# arduino-lockitron-nfc.net
KiCad netlist of a schematic drawn in EAGLE
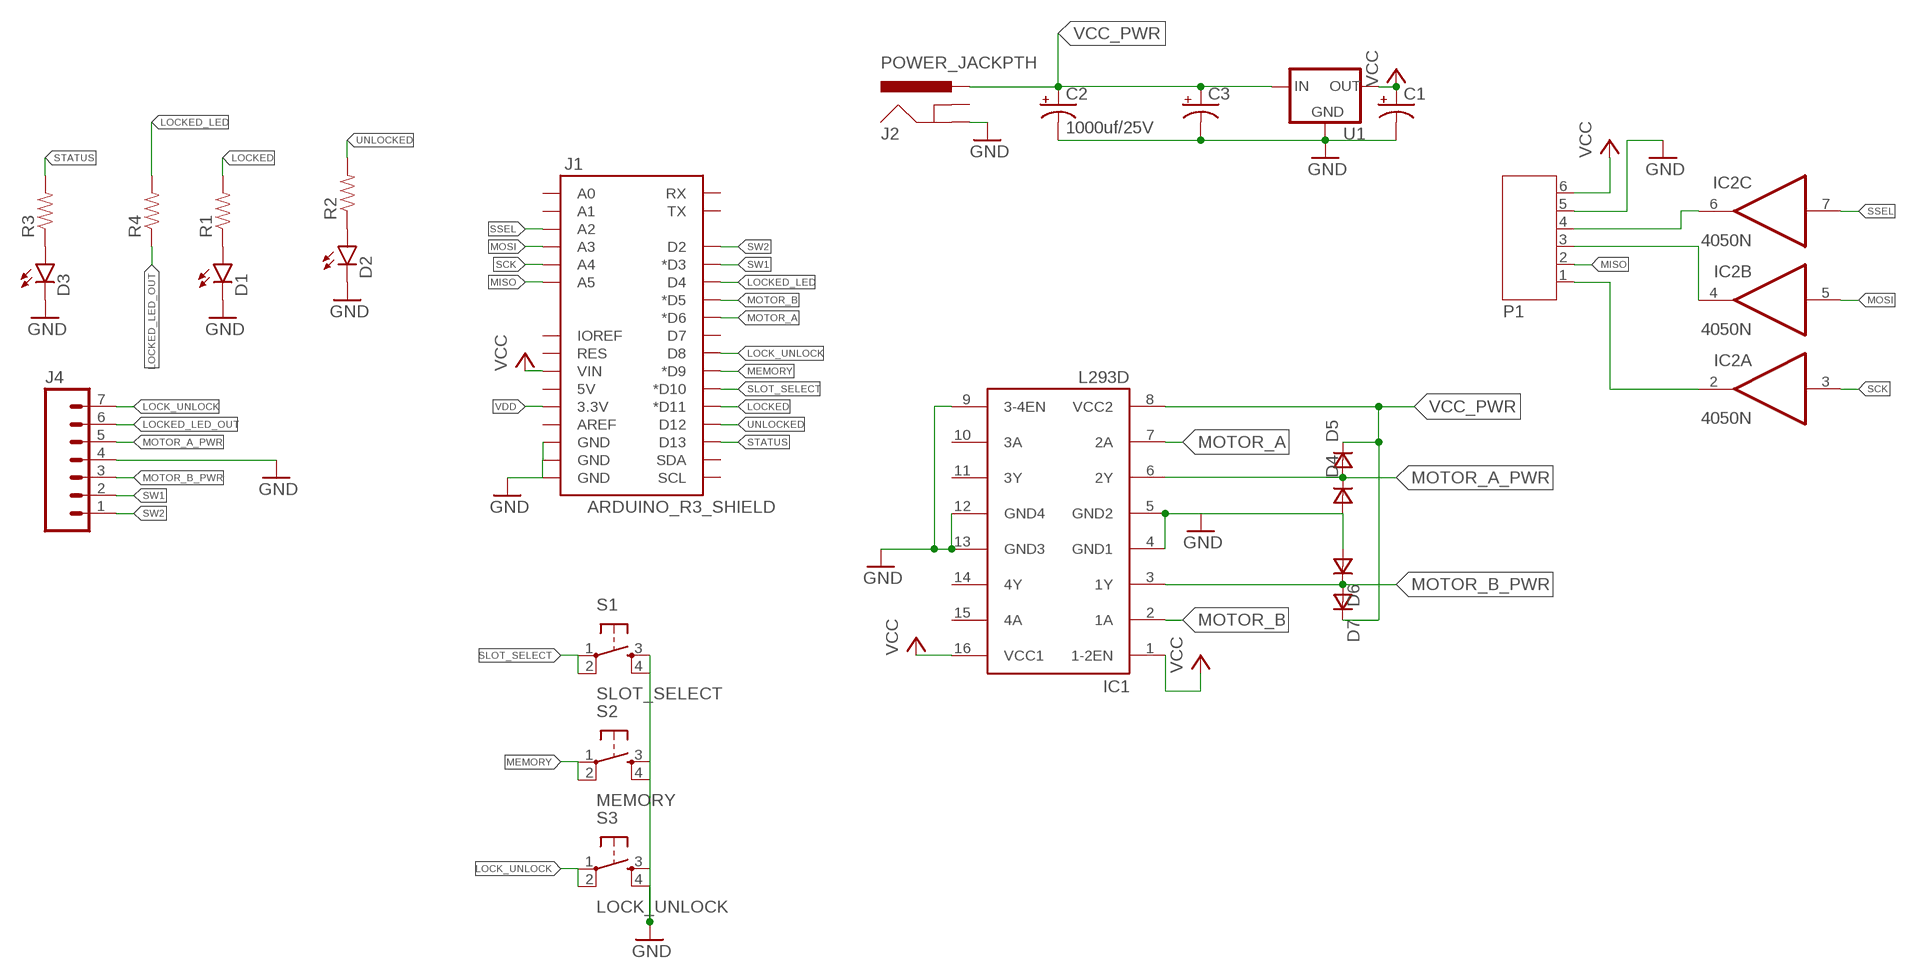
[diagram p0: schematic, sheet 1]

(export (version "E")
  (design (tool "Eeschema 10.0.6"))
  (components
    (comp (ref "C1")
      (value "47UF-50V-20%(ELECT)")
      (footprint "eagle-import:PANASONIC_D")
      (libsource (lib "eagle-import") (part "47UF-50V-20%(ELECT)"))
    )
    (comp (ref "C2")
      (value "1000uf/25V")
      (footprint "eagle-import:CPOL-RADIAL-1000UF-25V-KIT")
      (libsource (lib "eagle-import") (part "1000UF-25V(PTH)KIT"))
    )
    (comp (ref "C3")
      (value "47UF-50V-20%(ELECT)")
      (footprint "eagle-import:PANASONIC_D")
      (libsource (lib "eagle-import") (part "47UF-50V-20%(ELECT)"))
    )
    (comp (ref "D1")
      (value "LED0603")
      (footprint "eagle-import:LED-0603")
      (libsource (lib "eagle-import") (part "LED0603"))
    )
    (comp (ref "D2")
      (value "LED0603")
      (footprint "eagle-import:LED-0603")
      (libsource (lib "eagle-import") (part "LED0603"))
    )
    (comp (ref "D3")
      (value "LED0603")
      (footprint "eagle-import:LED-0603")
      (libsource (lib "eagle-import") (part "LED0603"))
    )
    (comp (ref "D4")
      (value "DSOD323")
      (footprint "eagle-import:SOD323")
      (fields (field (name "MPN") "CDSOD323-T05C"))
      (libsource (lib "eagle-import") (part "DSOD323"))
    )
    (comp (ref "D5")
      (value "DSOD323")
      (footprint "eagle-import:SOD323")
      (fields (field (name "MPN") "CDSOD323-T05C"))
      (libsource (lib "eagle-import") (part "DSOD323"))
    )
    (comp (ref "D6")
      (value "DSOD323")
      (footprint "eagle-import:SOD323")
      (fields (field (name "MPN") "CDSOD323-T05C"))
      (libsource (lib "eagle-import") (part "DSOD323"))
    )
    (comp (ref "D7")
      (value "DSOD323")
      (footprint "eagle-import:SOD323")
      (fields (field (name "MPN") "CDSOD323-T05C"))
      (libsource (lib "eagle-import") (part "DSOD323"))
    )
    (comp (ref "IC1")
      (value "L293D")
      (footprint "eagle-import:DIL16")
      (libsource (lib "eagle-import") (part "L293D"))
    )
    (comp (ref "IC2")
      (value "4050N")
      (footprint "eagle-import:DIL16")
      (libsource (lib "eagle-import") (part "4050N"))
    )
    (comp (ref "J1")
      (value "ARDUINO_R3_SHIELD")
      (footprint "eagle-import:UNO_R3_SHIELD")
      (libsource (lib "eagle-import") (part "ARDUINO_R3_SHIELD"))
    )
    (comp (ref "J2")
      (value "POWER_JACKPTH")
      (footprint "eagle-import:POWER_JACK_PTH")
      (libsource (lib "eagle-import") (part "POWER_JACKPTH"))
    )
    (comp (ref "J4")
      (value "M07LONGPADS")
      (footprint "eagle-import:1X07_LONGPADS")
      (libsource (lib "eagle-import") (part "M07LONGPADS"))
    )
    (comp (ref "P1")
      (value "JST-PH6")
      (footprint "eagle-import:JST-PH6")
      (libsource (lib "eagle-import") (part "JST-PH6"))
    )
    (comp (ref "R1")
      (value "RESISTOR0603")
      (footprint "eagle-import:0603-RES")
      (libsource (lib "eagle-import") (part "RESISTOR0603"))
    )
    (comp (ref "R2")
      (value "RESISTOR0603")
      (footprint "eagle-import:0603-RES")
      (libsource (lib "eagle-import") (part "RESISTOR0603"))
    )
    (comp (ref "R3")
      (value "RESISTOR0603")
      (footprint "eagle-import:0603-RES")
      (libsource (lib "eagle-import") (part "RESISTOR0603"))
    )
    (comp (ref "R4")
      (value "RESISTOR0603")
      (footprint "eagle-import:0603-RES")
      (libsource (lib "eagle-import") (part "RESISTOR0603"))
    )
    (comp (ref "S1")
      (value "SLOT_SELECT")
      (footprint "eagle-import:TACTILE-SWITCH-SMD")
      (libsource (lib "eagle-import") (part "TAC_SWITCHSMD"))
    )
    (comp (ref "S2")
      (value "MEMORY")
      (footprint "eagle-import:TACTILE-SWITCH-SMD")
      (libsource (lib "eagle-import") (part "TAC_SWITCHSMD"))
    )
    (comp (ref "S3")
      (value "LOCK_UNLOCK")
      (footprint "eagle-import:TACTILE-SWITCH-SMD")
      (libsource (lib "eagle-import") (part "TAC_SWITCHSMD"))
    )
    (comp (ref "U1")
      (value "V_REG_78XXSIDE")
      (footprint "eagle-import:78XXL")
      (libsource (lib "eagle-import") (part "V_REG_78XXSIDE"))
    )
  )
  (nets
    (net (code "1") (name "GND") (class "Default")
      (node (ref "C1") (pin "-") (pinfunction "-_-") (pintype "passive"))
      (node (ref "C2") (pin "-") (pinfunction "-_-") (pintype "passive"))
      (node (ref "C3") (pin "-") (pinfunction "-_-") (pintype "passive"))
      (node (ref "D1") (pin "C") (pinfunction "C_C") (pintype "passive"))
      (node (ref "D2") (pin "C") (pinfunction "C_C") (pintype "passive"))
      (node (ref "D3") (pin "C") (pinfunction "C_C") (pintype "passive"))
      (node (ref "D4") (pin "2") (pinfunction "A_2") (pintype "passive"))
      (node (ref "D6") (pin "2") (pinfunction "A_2") (pintype "passive"))
      (node (ref "IC1") (pin "12") (pinfunction "GND4_12") (pintype "power_in"))
      (node (ref "IC1") (pin "13") (pinfunction "GND3_13") (pintype "power_in"))
      (node (ref "IC1") (pin "4") (pinfunction "GND1_4") (pintype "power_in"))
      (node (ref "IC1") (pin "5") (pinfunction "GND2_5") (pintype "power_in"))
      (node (ref "IC1") (pin "9") (pinfunction "3-4EN_9") (pintype "input"))
      (node (ref "J1") (pin "GND@0") (pinfunction "GND_GND@0") (pintype "bidirectional"))
      (node (ref "J1") (pin "GND@1") (pinfunction "GND_GND@1") (pintype "bidirectional"))
      (node (ref "J1") (pin "GND@2") (pinfunction "GND_GND@2") (pintype "bidirectional"))
      (node (ref "J2") (pin "GND") (pinfunction "GND_GND") (pintype "bidirectional"))
      (node (ref "J4") (pin "4") (pinfunction "4_4") (pintype "passive"))
      (node (ref "P1") (pin "5") (pinfunction "5_5") (pintype "passive"))
      (node (ref "S1") (pin "3") (pinfunction "3_3") (pintype "passive"))
      (node (ref "S1") (pin "4") (pinfunction "4_4") (pintype "passive"))
      (node (ref "S2") (pin "3") (pinfunction "3_3") (pintype "passive"))
      (node (ref "S2") (pin "4") (pinfunction "4_4") (pintype "passive"))
      (node (ref "S3") (pin "3") (pinfunction "3_3") (pintype "passive"))
      (node (ref "S3") (pin "4") (pinfunction "4_4") (pintype "passive"))
      (node (ref "U1") (pin "GND") (pinfunction "GND_GND") (pintype "input"))
    )
    (net (code "2") (name "LOCKED") (class "Default")
      (node (ref "J1") (pin "D11") (pinfunction "*D11_D11") (pintype "bidirectional"))
      (node (ref "R1") (pin "2") (pinfunction "2_2") (pintype "passive"))
    )
    (net (code "3") (name "LOCKED_LED") (class "Default")
      (node (ref "J1") (pin "D4") (pinfunction "D4_D4") (pintype "bidirectional"))
      (node (ref "R4") (pin "2") (pinfunction "2_2") (pintype "passive"))
    )
    (net (code "4") (name "LOCKED_LED_OUT") (class "Default")
      (node (ref "J4") (pin "6") (pinfunction "6_6") (pintype "passive"))
      (node (ref "R4") (pin "1") (pinfunction "1_1") (pintype "passive"))
    )
    (net (code "5") (name "LOCK_UNLOCK") (class "Default")
      (node (ref "J1") (pin "D8") (pinfunction "D8_D8") (pintype "bidirectional"))
      (node (ref "J4") (pin "7") (pinfunction "7_7") (pintype "passive"))
      (node (ref "S3") (pin "1") (pinfunction "1_1") (pintype "passive"))
      (node (ref "S3") (pin "2") (pinfunction "2_2") (pintype "passive"))
    )
    (net (code "6") (name "MEMORY") (class "Default")
      (node (ref "J1") (pin "D9") (pinfunction "*D9_D9") (pintype "bidirectional"))
      (node (ref "S2") (pin "1") (pinfunction "1_1") (pintype "passive"))
      (node (ref "S2") (pin "2") (pinfunction "2_2") (pintype "passive"))
    )
    (net (code "7") (name "MISO") (class "Default")
      (node (ref "J1") (pin "A5") (pinfunction "A5_A5") (pintype "bidirectional"))
      (node (ref "P1") (pin "2") (pinfunction "2_2") (pintype "passive"))
    )
    (net (code "8") (name "MOSI") (class "Default")
      (node (ref "IC2") (pin "5") (pinfunction "I_5") (pintype "input"))
      (node (ref "J1") (pin "A3") (pinfunction "A3_A3") (pintype "bidirectional"))
    )
    (net (code "9") (name "MOTOR_A") (class "Default")
      (node (ref "IC1") (pin "7") (pinfunction "2A_7") (pintype "input"))
      (node (ref "J1") (pin "D6") (pinfunction "*D6_D6") (pintype "bidirectional"))
    )
    (net (code "10") (name "MOTOR_A_PWR") (class "Default")
      (node (ref "D4") (pin "1") (pinfunction "C_1") (pintype "passive"))
      (node (ref "D5") (pin "2") (pinfunction "A_2") (pintype "passive"))
      (node (ref "IC1") (pin "6") (pinfunction "2Y_6") (pintype "output"))
      (node (ref "J4") (pin "5") (pinfunction "5_5") (pintype "passive"))
    )
    (net (code "11") (name "MOTOR_B") (class "Default")
      (node (ref "IC1") (pin "2") (pinfunction "1A_2") (pintype "input"))
      (node (ref "J1") (pin "D5") (pinfunction "*D5_D5") (pintype "bidirectional"))
    )
    (net (code "12") (name "MOTOR_B_PWR") (class "Default")
      (node (ref "D6") (pin "1") (pinfunction "C_1") (pintype "passive"))
      (node (ref "D7") (pin "2") (pinfunction "A_2") (pintype "passive"))
      (node (ref "IC1") (pin "3") (pinfunction "1Y_3") (pintype "output"))
      (node (ref "J4") (pin "3") (pinfunction "3_3") (pintype "passive"))
    )
    (net (code "13") (name "Net-(D1-PadA)") (class "Default")
      (node (ref "D1") (pin "A") (pinfunction "A_A") (pintype "passive"))
      (node (ref "R1") (pin "1") (pinfunction "1_1") (pintype "passive"))
    )
    (net (code "14") (name "Net-(D2-PadA)") (class "Default")
      (node (ref "D2") (pin "A") (pinfunction "A_A") (pintype "passive"))
      (node (ref "R2") (pin "1") (pinfunction "1_1") (pintype "passive"))
    )
    (net (code "15") (name "Net-(D3-PadA)") (class "Default")
      (node (ref "D3") (pin "A") (pinfunction "A_A") (pintype "passive"))
      (node (ref "R3") (pin "1") (pinfunction "1_1") (pintype "passive"))
    )
    (net (code "16") (name "Net-(IC2A-O)") (class "Default")
      (node (ref "IC2") (pin "2") (pinfunction "O_2") (pintype "output"))
      (node (ref "P1") (pin "1") (pinfunction "1_1") (pintype "passive"))
    )
    (net (code "17") (name "Net-(IC2B-O)") (class "Default")
      (node (ref "IC2") (pin "4") (pinfunction "O_4") (pintype "output"))
      (node (ref "P1") (pin "3") (pinfunction "3_3") (pintype "passive"))
    )
    (net (code "18") (name "Net-(IC2C-O)") (class "Default")
      (node (ref "IC2") (pin "6") (pinfunction "O_6") (pintype "output"))
      (node (ref "P1") (pin "4") (pinfunction "4_4") (pintype "passive"))
    )
    (net (code "19") (name "SCK") (class "Default")
      (node (ref "IC2") (pin "3") (pinfunction "I_3") (pintype "input"))
      (node (ref "J1") (pin "A4") (pinfunction "A4_A4") (pintype "bidirectional"))
    )
    (net (code "20") (name "SLOT_SELECT") (class "Default")
      (node (ref "J1") (pin "D10") (pinfunction "*D10_D10") (pintype "bidirectional"))
      (node (ref "S1") (pin "1") (pinfunction "1_1") (pintype "passive"))
      (node (ref "S1") (pin "2") (pinfunction "2_2") (pintype "passive"))
    )
    (net (code "21") (name "SSEL") (class "Default")
      (node (ref "IC2") (pin "7") (pinfunction "I_7") (pintype "input"))
      (node (ref "J1") (pin "A2") (pinfunction "A2_A2") (pintype "bidirectional"))
    )
    (net (code "22") (name "STATUS") (class "Default")
      (node (ref "J1") (pin "D13") (pinfunction "D13_D13") (pintype "bidirectional"))
      (node (ref "R3") (pin "2") (pinfunction "2_2") (pintype "passive"))
    )
    (net (code "23") (name "SW1") (class "Default")
      (node (ref "J1") (pin "D3") (pinfunction "*D3_D3") (pintype "bidirectional"))
      (node (ref "J4") (pin "2") (pinfunction "2_2") (pintype "passive"))
    )
    (net (code "24") (name "SW2") (class "Default")
      (node (ref "J1") (pin "D2") (pinfunction "D2_D2") (pintype "bidirectional"))
      (node (ref "J4") (pin "1") (pinfunction "1_1") (pintype "passive"))
    )
    (net (code "25") (name "UNLOCKED") (class "Default")
      (node (ref "J1") (pin "D12") (pinfunction "D12_D12") (pintype "bidirectional"))
      (node (ref "R2") (pin "2") (pinfunction "2_2") (pintype "passive"))
    )
    (net (code "26") (name "VCC") (class "Default")
      (node (ref "C1") (pin "+") (pinfunction "+_+") (pintype "passive"))
      (node (ref "IC1") (pin "1") (pinfunction "1-2EN_1") (pintype "input"))
      (node (ref "IC1") (pin "16") (pinfunction "VCC1_16") (pintype "power_in"))
      (node (ref "J1") (pin "VIN") (pinfunction "VIN_VIN") (pintype "bidirectional"))
      (node (ref "P1") (pin "6") (pinfunction "6_6") (pintype "passive"))
      (node (ref "U1") (pin "OUT") (pinfunction "OUT_OUT") (pintype "passive"))
    )
    (net (code "27") (name "VCC_PWR") (class "Default")
      (node (ref "C2") (pin "+") (pinfunction "+_+") (pintype "passive"))
      (node (ref "C3") (pin "+") (pinfunction "+_+") (pintype "passive"))
      (node (ref "D5") (pin "1") (pinfunction "C_1") (pintype "passive"))
      (node (ref "D7") (pin "1") (pinfunction "C_1") (pintype "passive"))
      (node (ref "IC1") (pin "8") (pinfunction "VCC2_8") (pintype "power_in"))
      (node (ref "J2") (pin "PWR") (pinfunction "PWR_PWR") (pintype "bidirectional"))
      (node (ref "U1") (pin "IN") (pinfunction "IN_IN") (pintype "input"))
    )
    (net (code "28") (name "VDD") (class "Default")
      (node (ref "J1") (pin "3.3V") (pinfunction "3.3V_3.3V") (pintype "bidirectional"))
    )
    (net (code "29") (name "unconnected-(IC1-3A-Pad10)") (class "Default")
      (node (ref "IC1") (pin "10") (pinfunction "3A_10") (pintype "input"))
    )
    (net (code "30") (name "unconnected-(IC1-3Y-Pad11)") (class "Default")
      (node (ref "IC1") (pin "11") (pinfunction "3Y_11") (pintype "output"))
    )
    (net (code "31") (name "unconnected-(IC1-4A-Pad15)") (class "Default")
      (node (ref "IC1") (pin "15") (pinfunction "4A_15") (pintype "input"))
    )
    (net (code "32") (name "unconnected-(IC1-4Y-Pad14)") (class "Default")
      (node (ref "IC1") (pin "14") (pinfunction "4Y_14") (pintype "output"))
    )
    (net (code "33") (name "unconnected-(J1-Pad5V)") (class "Default")
      (node (ref "J1") (pin "5V") (pinfunction "5V_5V") (pintype "bidirectional"))
    )
    (net (code "34") (name "unconnected-(J1-PadA0)") (class "Default")
      (node (ref "J1") (pin "A0") (pinfunction "A0_A0") (pintype "bidirectional"))
    )
    (net (code "35") (name "unconnected-(J1-PadA1)") (class "Default")
      (node (ref "J1") (pin "A1") (pinfunction "A1_A1") (pintype "bidirectional"))
    )
    (net (code "36") (name "unconnected-(J1-PadAREF)") (class "Default")
      (node (ref "J1") (pin "AREF") (pinfunction "AREF_AREF") (pintype "bidirectional"))
    )
    (net (code "37") (name "unconnected-(J1-PadD7)") (class "Default")
      (node (ref "J1") (pin "D7") (pinfunction "D7_D7") (pintype "bidirectional"))
    )
    (net (code "38") (name "unconnected-(J1-PadIOREF)") (class "Default")
      (node (ref "J1") (pin "IOREF") (pinfunction "IOREF_IOREF") (pintype "bidirectional"))
    )
    (net (code "39") (name "unconnected-(J1-PadRES)") (class "Default")
      (node (ref "J1") (pin "RES") (pinfunction "RES_RES") (pintype "bidirectional"))
    )
    (net (code "40") (name "unconnected-(J1-PadRX)") (class "Default")
      (node (ref "J1") (pin "RX") (pinfunction "RX_RX") (pintype "bidirectional"))
    )
    (net (code "41") (name "unconnected-(J1-PadSCL)") (class "Default")
      (node (ref "J1") (pin "SCL") (pinfunction "SCL_SCL") (pintype "bidirectional"))
    )
    (net (code "42") (name "unconnected-(J1-PadSDA)") (class "Default")
      (node (ref "J1") (pin "SDA") (pinfunction "SDA_SDA") (pintype "bidirectional"))
    )
    (net (code "43") (name "unconnected-(J1-PadTX)") (class "Default")
      (node (ref "J1") (pin "TX") (pinfunction "TX_TX") (pintype "bidirectional"))
    )
    (net (code "44") (name "unconnected-(J2-PadGNDBREAK)") (class "Default")
      (node (ref "J2") (pin "GNDBREAK") (pinfunction "GNDBREAK_GNDBREAK") (pintype "bidirectional"))
    )
  )
)
